# LN_LDO.net
KiCad netlist of a schematic drawn in Altium Designer
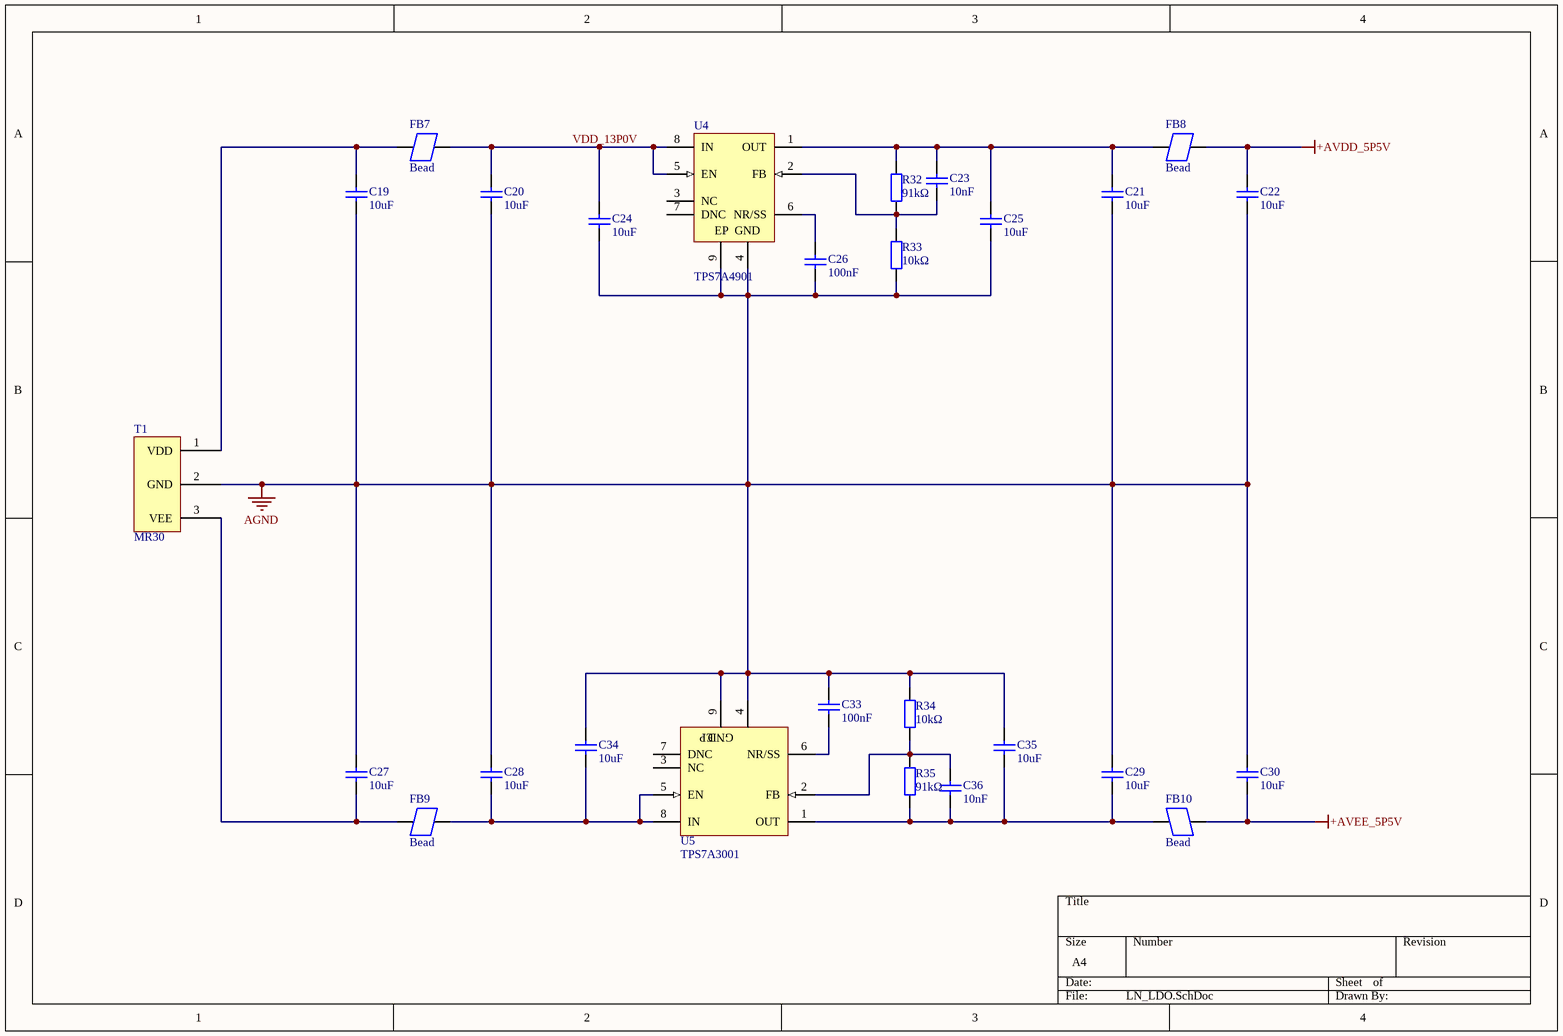
[diagram p0: LN_LDO.SchDoc]

(export (version "E")
  (design (tool "Eeschema 10.0.6"))
  (components
    (comp (ref "C19")
      (value "10uF")
      (footprint "0805_C")
      (description "贴片电容")
      (libsource (lib "Miscellaneous Devices LC") (part "0805 10uF (106) 10% 25V"))
    )
    (comp (ref "C20")
      (value "10uF")
      (footprint "0805_C")
      (description "贴片电容")
      (libsource (lib "Miscellaneous Devices LC") (part "0805 10uF (106) 10% 25V"))
    )
    (comp (ref "C21")
      (value "10uF")
      (footprint "0805_C")
      (description "贴片电容")
      (libsource (lib "Miscellaneous Devices LC") (part "0805 10uF (106) 10% 25V"))
    )
    (comp (ref "C22")
      (value "10uF")
      (footprint "0805_C")
      (description "贴片电容")
      (libsource (lib "Miscellaneous Devices LC") (part "0805 10uF (106) 10% 25V"))
    )
    (comp (ref "C23")
      (value "10nF")
      (footprint "0603_C")
      (description "贴片电容")
      (libsource (lib "Miscellaneous Devices LC") (part "0603 10nF (103) 10% 50V"))
    )
    (comp (ref "C24")
      (value "10uF")
      (footprint "0805_C")
      (description "贴片电容")
      (libsource (lib "Miscellaneous Devices LC") (part "0805 10uF (106) 10% 25V"))
    )
    (comp (ref "C25")
      (value "10uF")
      (footprint "0805_C")
      (description "贴片电容")
      (libsource (lib "Miscellaneous Devices LC") (part "0805 10uF (106) 10% 25V"))
    )
    (comp (ref "C26")
      (value "100nF")
      (footprint "0603_C")
      (description "贴片电容")
      (libsource (lib "Miscellaneous Devices LC") (part "0603 100nF (104) 10% 50V"))
    )
    (comp (ref "C27")
      (value "10uF")
      (footprint "0805_C")
      (description "贴片电容")
      (libsource (lib "Miscellaneous Devices LC") (part "0805 10uF (106) 10% 25V"))
    )
    (comp (ref "C28")
      (value "10uF")
      (footprint "0805_C")
      (description "贴片电容")
      (libsource (lib "Miscellaneous Devices LC") (part "0805 10uF (106) 10% 25V"))
    )
    (comp (ref "C29")
      (value "10uF")
      (footprint "0805_C")
      (description "贴片电容")
      (libsource (lib "Miscellaneous Devices LC") (part "0805 10uF (106) 10% 25V"))
    )
    (comp (ref "C30")
      (value "10uF")
      (footprint "0805_C")
      (description "贴片电容")
      (libsource (lib "Miscellaneous Devices LC") (part "0805 10uF (106) 10% 25V"))
    )
    (comp (ref "C33")
      (value "100nF")
      (footprint "0603_C")
      (description "贴片电容")
      (libsource (lib "Miscellaneous Devices LC") (part "0603 100nF (104) 10% 50V"))
    )
    (comp (ref "C34")
      (value "10uF")
      (footprint "0805_C")
      (description "贴片电容")
      (libsource (lib "Miscellaneous Devices LC") (part "0805 10uF (106) 10% 25V"))
    )
    (comp (ref "C35")
      (value "10uF")
      (footprint "0805_C")
      (description "贴片电容")
      (libsource (lib "Miscellaneous Devices LC") (part "0805 10uF (106) 10% 25V"))
    )
    (comp (ref "C36")
      (value "10nF")
      (footprint "0603_C")
      (description "贴片电容")
      (libsource (lib "Miscellaneous Devices LC") (part "0603 10nF (103) 10% 50V"))
    )
    (comp (ref "FB7") (value "Bead") (footprint "0805_L") (libsource (lib "OlvkLib") (part "Bead")))
    (comp (ref "FB8") (value "Bead") (footprint "0805_L") (libsource (lib "OlvkLib") (part "Bead")))
    (comp (ref "FB9") (value "Bead") (footprint "0805_L") (libsource (lib "OlvkLib") (part "Bead")))
    (comp (ref "FB10") (value "Bead") (footprint "0805_L") (libsource (lib "OlvkLib") (part "Bead")))
    (comp (ref "R32")
      (value "91kΩ")
      (footprint "0603_R")
      (description "贴片电阻")
      (libsource (lib "Miscellaneous Devices LC") (part "0603 91KΩ (9102) 1%"))
    )
    (comp (ref "R33")
      (value "10kΩ")
      (footprint "0603_R")
      (description "贴片电阻")
      (libsource (lib "") (part "0603 10KΩ (1002) 1%_1"))
    )
    (comp (ref "R34")
      (value "10kΩ")
      (footprint "0603_R")
      (description "贴片电阻")
      (libsource (lib "Miscellaneous Devices LC") (part "0603 10KΩ (1002) 1%"))
    )
    (comp (ref "R35")
      (value "91kΩ")
      (footprint "0603_R")
      (description "贴片电阻")
      (libsource (lib "") (part "0603 91KΩ (9102) 1%_1"))
    )
    (comp (ref "T1") (value "MR30") (footprint "MR30PW-M") (libsource (lib "OlvkLib") (part "MR30")))
    (comp (ref "U4")
      (value "TPS7A4901")
      (footprint "DGN0008D_L")
      (libsource (lib "Schlib1") (part "TPS7A4901"))
    )
    (comp (ref "U5")
      (value "TPS7A3001")
      (footprint "DGN0008D_L")
      (libsource (lib "Schlib1") (part "TPS7A3001"))
    )
  )
  (nets
    (net (code "1") (name "+AVDD_5P5V") (class "Default")
      (node (ref "C22") (pin "2") (pinfunction "2_2") (pintype "passive"))
      (node (ref "FB8") (pin "1") (pinfunction "1_1") (pintype "passive"))
    )
    (net (code "2") (name "+AVEE_5P5V") (class "Default")
      (node (ref "C30") (pin "1") (pinfunction "1_1") (pintype "passive"))
      (node (ref "FB10") (pin "1") (pinfunction "1_1") (pintype "passive"))
    )
    (net (code "3") (name "/VDD_13P0V") (class "Default")
      (node (ref "C20") (pin "2") (pinfunction "2_2") (pintype "passive"))
      (node (ref "C24") (pin "2") (pinfunction "2_2") (pintype "passive"))
      (node (ref "FB7") (pin "1") (pinfunction "1_1") (pintype "passive"))
      (node (ref "U4") (pin "5") (pinfunction "EN_5") (pintype "input"))
      (node (ref "U4") (pin "8") (pinfunction "IN_8") (pintype "power_in"))
    )
    (net (code "4") (name "AGND") (class "Default")
      (node (ref "C19") (pin "1") (pinfunction "1_1") (pintype "passive"))
      (node (ref "C20") (pin "1") (pinfunction "1_1") (pintype "passive"))
      (node (ref "C21") (pin "1") (pinfunction "1_1") (pintype "passive"))
      (node (ref "C22") (pin "1") (pinfunction "1_1") (pintype "passive"))
      (node (ref "C24") (pin "1") (pinfunction "1_1") (pintype "passive"))
      (node (ref "C25") (pin "1") (pinfunction "1_1") (pintype "passive"))
      (node (ref "C26") (pin "1") (pinfunction "1_1") (pintype "passive"))
      (node (ref "C27") (pin "2") (pinfunction "2_2") (pintype "passive"))
      (node (ref "C28") (pin "2") (pinfunction "2_2") (pintype "passive"))
      (node (ref "C29") (pin "2") (pinfunction "2_2") (pintype "passive"))
      (node (ref "C30") (pin "2") (pinfunction "2_2") (pintype "passive"))
      (node (ref "C33") (pin "1") (pinfunction "1_1") (pintype "passive"))
      (node (ref "C34") (pin "1") (pinfunction "1_1") (pintype "passive"))
      (node (ref "C35") (pin "1") (pinfunction "1_1") (pintype "passive"))
      (node (ref "R33") (pin "1") (pinfunction "1_1") (pintype "passive"))
      (node (ref "R34") (pin "1") (pinfunction "1_1") (pintype "passive"))
      (node (ref "T1") (pin "2") (pinfunction "GND_2") (pintype "power_in"))
      (node (ref "U4") (pin "4") (pinfunction "GND_4") (pintype "power_in"))
      (node (ref "U4") (pin "9") (pinfunction "EP_9") (pintype "power_in"))
      (node (ref "U5") (pin "4") (pinfunction "GND_4") (pintype "power_in"))
      (node (ref "U5") (pin "9") (pinfunction "EP_9") (pintype "passive"))
    )
    (net (code "5") (name "Net-(T1-VDD)") (class "Default")
      (node (ref "C19") (pin "2") (pinfunction "2_2") (pintype "passive"))
      (node (ref "FB7") (pin "2") (pinfunction "2_2") (pintype "passive"))
      (node (ref "T1") (pin "1") (pinfunction "VDD_1") (pintype "power_in"))
    )
    (net (code "6") (name "Net-(T1-VEE)") (class "Default")
      (node (ref "C27") (pin "1") (pinfunction "1_1") (pintype "passive"))
      (node (ref "FB9") (pin "1") (pinfunction "1_1") (pintype "passive"))
      (node (ref "T1") (pin "3") (pinfunction "VEE_3") (pintype "power_in"))
    )
    (net (code "7") (name "Net-(U4-FB)") (class "Default")
      (node (ref "C23") (pin "1") (pinfunction "1_1") (pintype "passive"))
      (node (ref "R32") (pin "1") (pinfunction "1_1") (pintype "passive"))
      (node (ref "R33") (pin "2") (pinfunction "2_2") (pintype "passive"))
      (node (ref "U4") (pin "2") (pinfunction "FB_2") (pintype "input"))
    )
    (net (code "8") (name "Net-(U4-NR{slash}SS)") (class "Default")
      (node (ref "C26") (pin "2") (pinfunction "2_2") (pintype "passive"))
      (node (ref "U4") (pin "6") (pinfunction "NR/SS_6") (pintype "passive"))
    )
    (net (code "9") (name "Net-(U4-OUT)") (class "Default")
      (node (ref "C21") (pin "2") (pinfunction "2_2") (pintype "passive"))
      (node (ref "C23") (pin "2") (pinfunction "2_2") (pintype "passive"))
      (node (ref "C25") (pin "2") (pinfunction "2_2") (pintype "passive"))
      (node (ref "FB8") (pin "2") (pinfunction "2_2") (pintype "passive"))
      (node (ref "R32") (pin "2") (pinfunction "2_2") (pintype "passive"))
      (node (ref "U4") (pin "1") (pinfunction "OUT_1") (pintype "power_in"))
    )
    (net (code "10") (name "Net-(U5-EN)") (class "Default")
      (node (ref "C28") (pin "1") (pinfunction "1_1") (pintype "passive"))
      (node (ref "C34") (pin "2") (pinfunction "2_2") (pintype "passive"))
      (node (ref "FB9") (pin "2") (pinfunction "2_2") (pintype "passive"))
      (node (ref "U5") (pin "5") (pinfunction "EN_5") (pintype "input"))
      (node (ref "U5") (pin "8") (pinfunction "IN_8") (pintype "power_in"))
    )
    (net (code "11") (name "Net-(U5-FB)") (class "Default")
      (node (ref "C36") (pin "1") (pinfunction "1_1") (pintype "passive"))
      (node (ref "R34") (pin "2") (pinfunction "2_2") (pintype "passive"))
      (node (ref "R35") (pin "1") (pinfunction "1_1") (pintype "passive"))
      (node (ref "U5") (pin "2") (pinfunction "FB_2") (pintype "input"))
    )
    (net (code "12") (name "Net-(U5-NR{slash}SS)") (class "Default")
      (node (ref "C33") (pin "2") (pinfunction "2_2") (pintype "passive"))
      (node (ref "U5") (pin "6") (pinfunction "NR/SS_6") (pintype "passive"))
    )
    (net (code "13") (name "Net-(U5-OUT)") (class "Default")
      (node (ref "C29") (pin "1") (pinfunction "1_1") (pintype "passive"))
      (node (ref "C35") (pin "2") (pinfunction "2_2") (pintype "passive"))
      (node (ref "C36") (pin "2") (pinfunction "2_2") (pintype "passive"))
      (node (ref "FB10") (pin "2") (pinfunction "2_2") (pintype "passive"))
      (node (ref "R35") (pin "2") (pinfunction "2_2") (pintype "passive"))
      (node (ref "U5") (pin "1") (pinfunction "OUT_1") (pintype "power_in"))
    )
    (net (code "14") (name "unconnected-(U4-DNC-Pad7)") (class "Default")
      (node (ref "U4") (pin "7") (pinfunction "DNC_7") (pintype "passive"))
    )
    (net (code "15") (name "unconnected-(U4-NC-Pad3)") (class "Default")
      (node (ref "U4") (pin "3") (pinfunction "NC_3") (pintype "passive"))
    )
    (net (code "16") (name "unconnected-(U5-DNC-Pad7)") (class "Default")
      (node (ref "U5") (pin "7") (pinfunction "DNC_7") (pintype "passive"))
    )
    (net (code "17") (name "unconnected-(U5-NC-Pad3)") (class "Default")
      (node (ref "U5") (pin "3") (pinfunction "NC_3") (pintype "passive"))
    )
  )
)
